# AC_controller_2020-08-26_13-25-38.net
KiCad netlist of a schematic drawn in EasyEDA
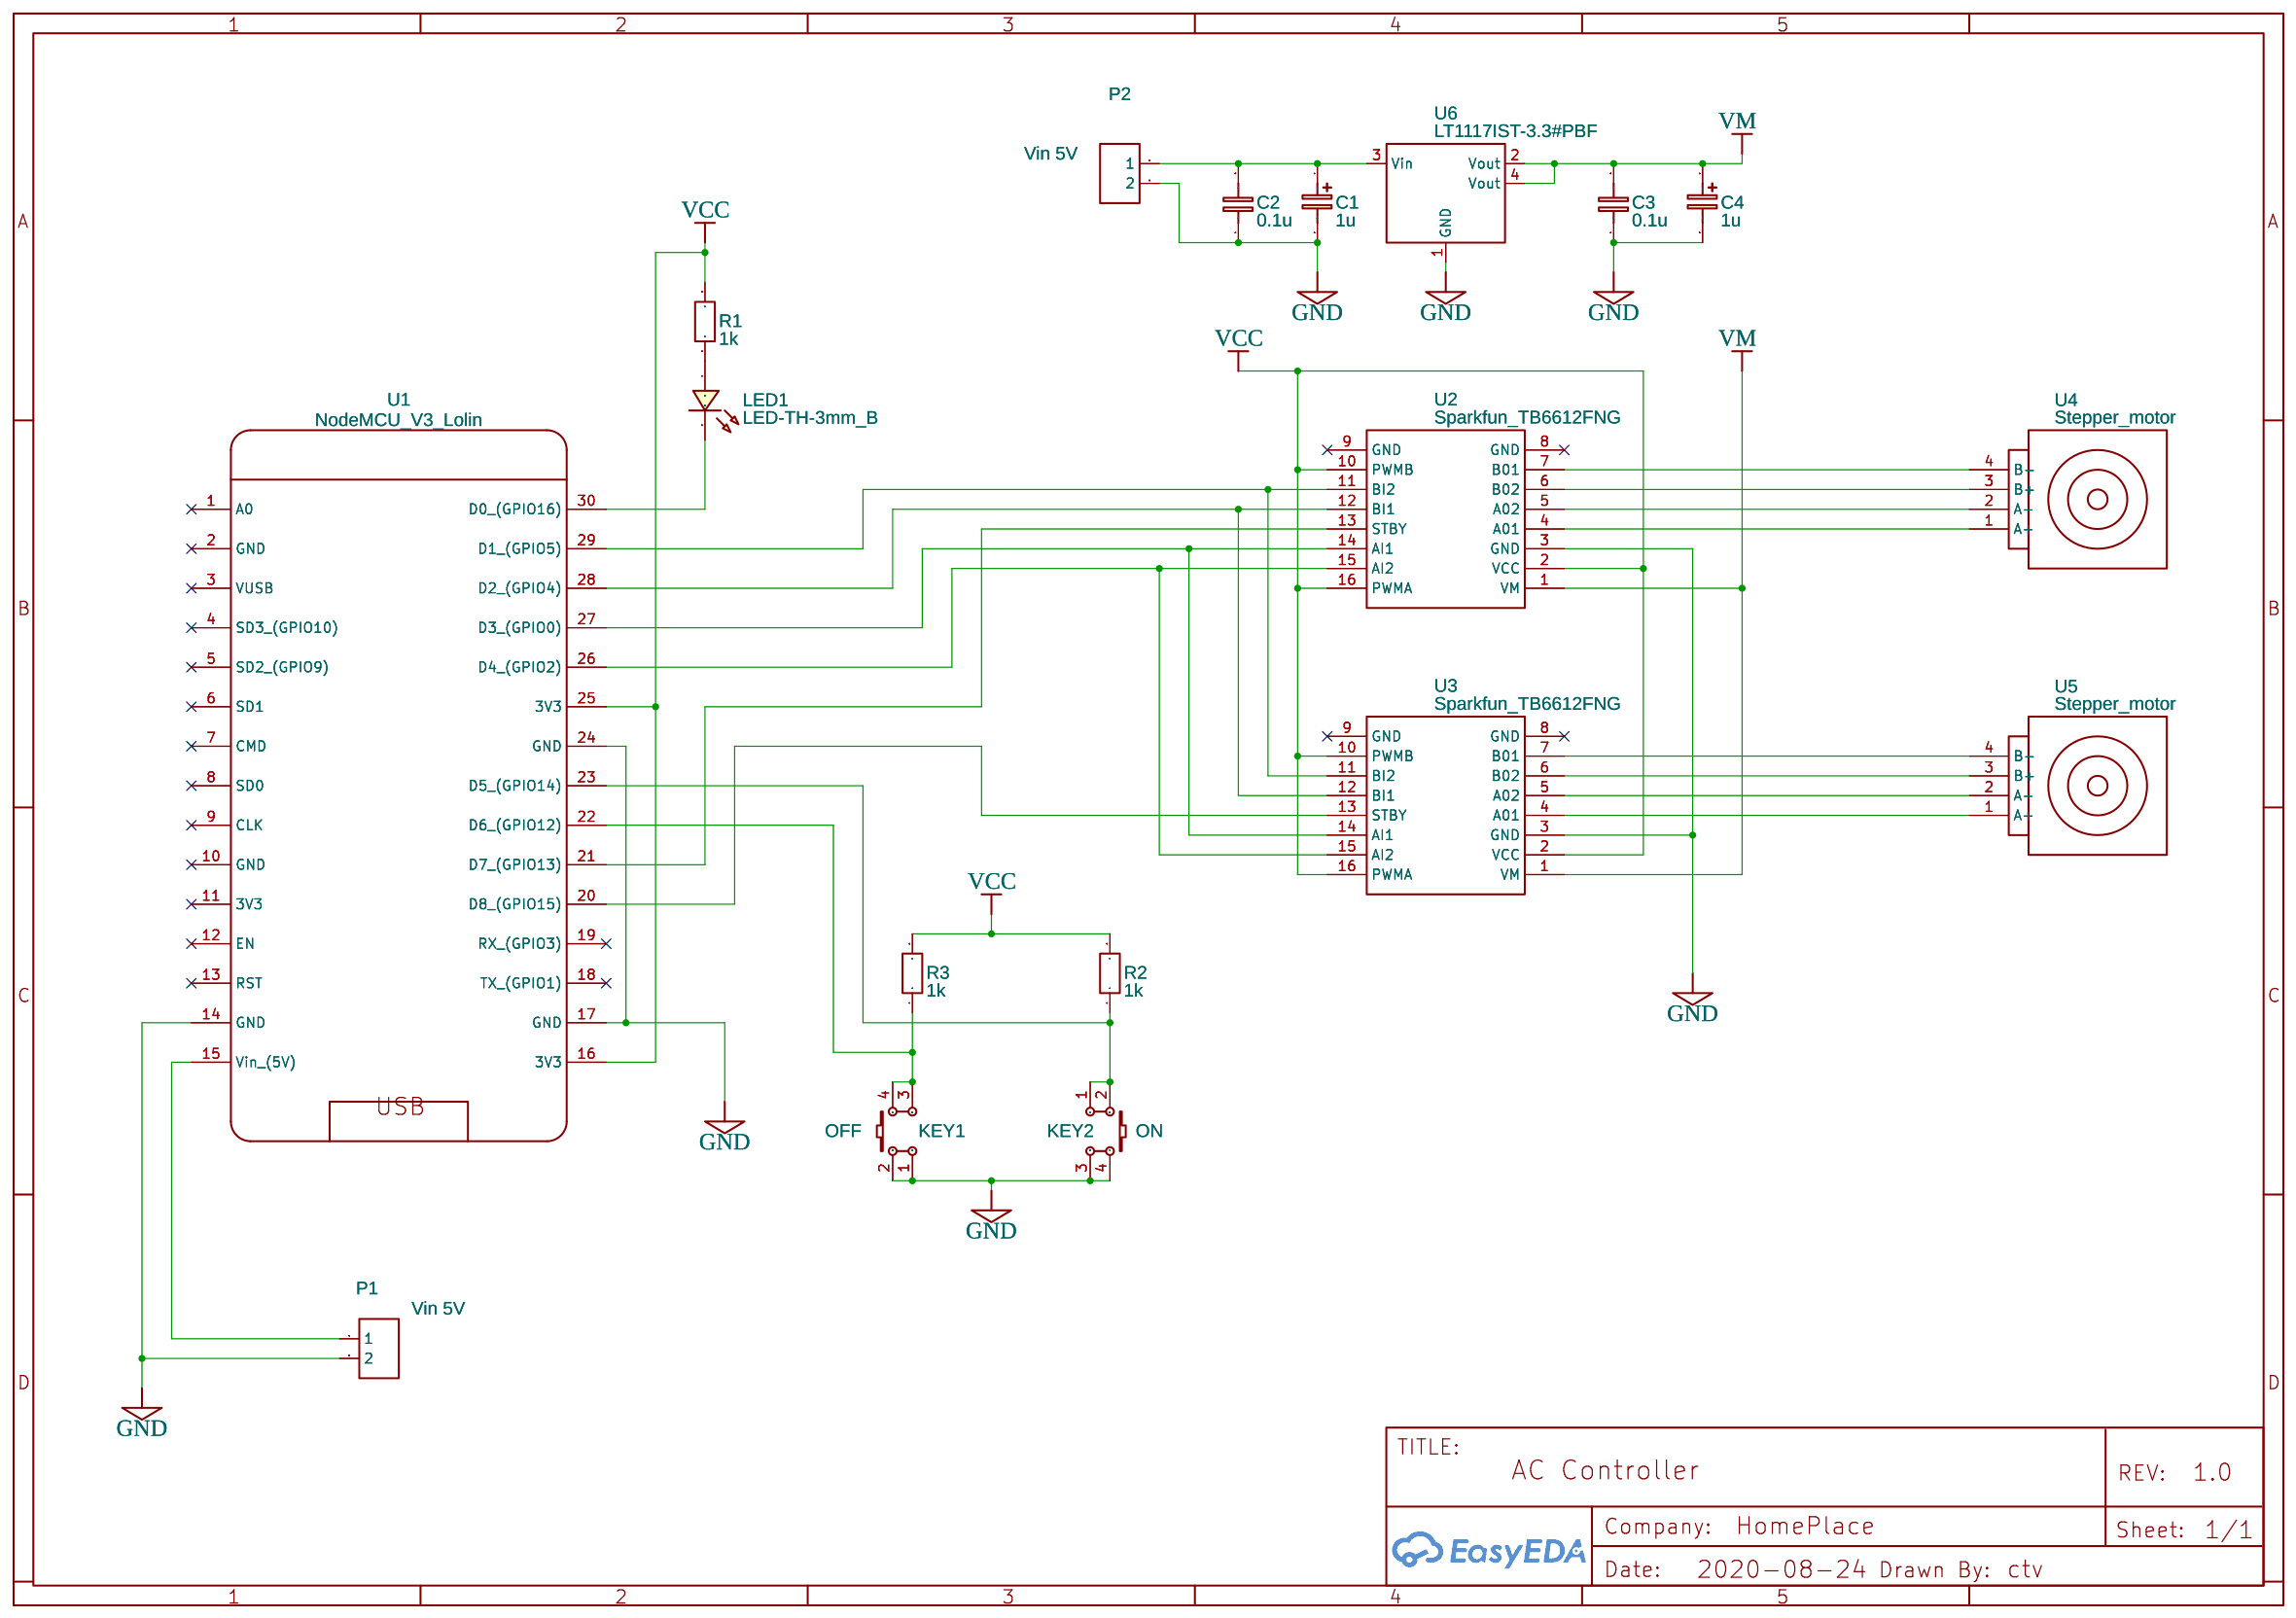
[diagram p0: schematic sheet]

(export (version "E")
  (design (tool "Eeschema 10.0.6"))
  (components
    (comp (ref "C1") (value "1u") (libsource (lib "") (part "C_Tan_SMD_A_EU")))
    (comp (ref "C2") (value "0.1u") (libsource (lib "") (part "C_0603_EU")))
    (comp (ref "C3") (value "0.1u") (libsource (lib "") (part "C_0603_EU")))
    (comp (ref "C4") (value "1u") (libsource (lib "") (part "C_Tan_SMD_A_EU")))
    (comp (ref "KEY1")
      (value "OFF")
      (fields
        (field (name "BOM_Manufacturer Part") "K2-1103DP-M4SW-04")
        (field (name "BOM_Supplier Part") "C128053")
      )
      (libsource (lib "") (part "K4-12×12_TH"))
    )
    (comp (ref "KEY2")
      (value "ON")
      (fields
        (field (name "BOM_Manufacturer Part") "K2-1103DP-M4SW-04")
        (field (name "BOM_Supplier Part") "C128053")
      )
      (libsource (lib "") (part "K4-12×12_TH_1"))
    )
    (comp (ref "LED1")
      (value "LED-TH-3mm_B")
      (fields
        (field (name "BOM_Manufacturer Part") "204-10SUBC/S400-A4")
        (field (name "BOM_Supplier Part") "C86881")
      )
      (libsource (lib "") (part "LED-TH-3mm_B"))
    )
    (comp (ref "P1") (value "Vin 5V") (libsource (lib "") (part "CONN-TH_2P-P5.08_1")))
    (comp (ref "P2") (value "Vin 5V") (libsource (lib "") (part "CONN-TH_2P-P5.08")))
    (comp (ref "R1") (value "1k") (libsource (lib "") (part "R_0603_EU")))
    (comp (ref "R2") (value "1k") (libsource (lib "") (part "R_0603_EU")))
    (comp (ref "R3") (value "1k") (libsource (lib "") (part "R_0603_EU")))
    (comp (ref "U1")
      (value "NodeMCU_V3_Lolin")
      (fields (field (name "BOM_Manufacturer Part") "NodeMCU ESP8266-12E Amica V2"))
      (libsource (lib "") (part "NodeMCU_ESP8266-12E_Lolin"))
    )
    (comp (ref "U2") (value "Sparkfun_TB6612FNG") (libsource (lib "") (part "Sparkfun_TB6612FNG")))
    (comp (ref "U3") (value "Sparkfun_TB6612FNG") (libsource (lib "") (part "Sparkfun_TB6612FNG")))
    (comp (ref "U4")
      (value "Stepper_motor")
      (fields (field (name "BOM_Manufacturer Part") "NEMA 23 Stepper Motor"))
      (libsource (lib "") (part "Stepper_motor"))
    )
    (comp (ref "U5")
      (value "Stepper_motor")
      (fields (field (name "BOM_Manufacturer Part") "NEMA 23 Stepper Motor"))
      (libsource (lib "") (part "Stepper_motor"))
    )
    (comp (ref "U6")
      (value "LT1117IST-3.3#PBF")
      (fields (field (name "BOM_Supplier Part") "C114908"))
      (libsource (lib "") (part "LT1117IST-3.3#PBF"))
    )
  )
  (nets
    (net (code "1") (name "GND") (class "Default")
      (node (ref "C1") (pin "2") (pinfunction "2_2") (pintype "unspecified"))
      (node (ref "C2") (pin "1") (pinfunction "1_1") (pintype "unspecified"))
      (node (ref "C3") (pin "1") (pinfunction "1_1") (pintype "unspecified"))
      (node (ref "C4") (pin "2") (pinfunction "2_2") (pintype "unspecified"))
      (node (ref "KEY1") (pin "1") (pinfunction "1_1") (pintype "unspecified"))
      (node (ref "KEY1") (pin "2") (pinfunction "2_2") (pintype "unspecified"))
      (node (ref "KEY2") (pin "3") (pinfunction "3_3") (pintype "unspecified"))
      (node (ref "KEY2") (pin "4") (pinfunction "4_4") (pintype "unspecified"))
      (node (ref "P1") (pin "2") (pinfunction "2_2") (pintype "unspecified"))
      (node (ref "P2") (pin "2") (pinfunction "2_2") (pintype "unspecified"))
      (node (ref "U1") (pin "14") (pinfunction "GND_14") (pintype "unspecified"))
      (node (ref "U1") (pin "17") (pinfunction "GND_17") (pintype "unspecified"))
      (node (ref "U1") (pin "24") (pinfunction "GND_24") (pintype "unspecified"))
      (node (ref "U2") (pin "3") (pinfunction "GND_3") (pintype "unspecified"))
      (node (ref "U3") (pin "3") (pinfunction "GND_3") (pintype "unspecified"))
      (node (ref "U6") (pin "1") (pinfunction "GND_1") (pintype "unspecified"))
    )
    (net (code "2") (name "Net-(LED1-Pad1)") (class "Default")
      (node (ref "LED1") (pin "1") (pinfunction "1_1") (pintype "unspecified"))
      (node (ref "R1") (pin "1") (pinfunction "1_1") (pintype "unspecified"))
    )
    (net (code "3") (name "Net-(U1-D0_(GPIO16))") (class "Default")
      (node (ref "LED1") (pin "2") (pinfunction "2_2") (pintype "unspecified"))
      (node (ref "U1") (pin "30") (pinfunction "D0_(GPIO16)_30") (pintype "unspecified"))
    )
    (net (code "4") (name "Net-(U1-D1_(GPIO5))") (class "Default")
      (node (ref "U1") (pin "29") (pinfunction "D1_(GPIO5)_29") (pintype "unspecified"))
      (node (ref "U2") (pin "11") (pinfunction "BI2_11") (pintype "unspecified"))
      (node (ref "U3") (pin "11") (pinfunction "BI2_11") (pintype "unspecified"))
    )
    (net (code "5") (name "Net-(U1-D2_(GPIO4))") (class "Default")
      (node (ref "U1") (pin "28") (pinfunction "D2_(GPIO4)_28") (pintype "unspecified"))
      (node (ref "U2") (pin "12") (pinfunction "BI1_12") (pintype "unspecified"))
      (node (ref "U3") (pin "12") (pinfunction "BI1_12") (pintype "unspecified"))
    )
    (net (code "6") (name "Net-(U1-D3_(GPIO0))") (class "Default")
      (node (ref "U1") (pin "27") (pinfunction "D3_(GPIO0)_27") (pintype "unspecified"))
      (node (ref "U2") (pin "14") (pinfunction "AI1_14") (pintype "unspecified"))
      (node (ref "U3") (pin "14") (pinfunction "AI1_14") (pintype "unspecified"))
    )
    (net (code "7") (name "Net-(U1-D4_(GPIO2))") (class "Default")
      (node (ref "U1") (pin "26") (pinfunction "D4_(GPIO2)_26") (pintype "unspecified"))
      (node (ref "U2") (pin "15") (pinfunction "AI2_15") (pintype "unspecified"))
      (node (ref "U3") (pin "15") (pinfunction "AI2_15") (pintype "unspecified"))
    )
    (net (code "8") (name "Net-(U1-D5_(GPIO14))") (class "Default")
      (node (ref "KEY2") (pin "1") (pinfunction "1_1") (pintype "unspecified"))
      (node (ref "KEY2") (pin "2") (pinfunction "2_2") (pintype "unspecified"))
      (node (ref "R2") (pin "1") (pinfunction "1_1") (pintype "unspecified"))
      (node (ref "U1") (pin "23") (pinfunction "D5_(GPIO14)_23") (pintype "unspecified"))
    )
    (net (code "9") (name "Net-(U1-D6_(GPIO12))") (class "Default")
      (node (ref "KEY1") (pin "3") (pinfunction "3_3") (pintype "unspecified"))
      (node (ref "KEY1") (pin "4") (pinfunction "4_4") (pintype "unspecified"))
      (node (ref "R3") (pin "1") (pinfunction "1_1") (pintype "unspecified"))
      (node (ref "U1") (pin "22") (pinfunction "D6_(GPIO12)_22") (pintype "unspecified"))
    )
    (net (code "10") (name "Net-(U1-D7_(GPIO13))") (class "Default")
      (node (ref "U1") (pin "21") (pinfunction "D7_(GPIO13)_21") (pintype "unspecified"))
      (node (ref "U2") (pin "13") (pinfunction "STBY_13") (pintype "unspecified"))
    )
    (net (code "11") (name "Net-(U1-D8_(GPIO15))") (class "Default")
      (node (ref "U1") (pin "20") (pinfunction "D8_(GPIO15)_20") (pintype "unspecified"))
      (node (ref "U3") (pin "13") (pinfunction "STBY_13") (pintype "unspecified"))
    )
    (net (code "12") (name "Net-(U1-Vin_(5V))") (class "Default")
      (node (ref "P1") (pin "1") (pinfunction "1_1") (pintype "unspecified"))
      (node (ref "U1") (pin "15") (pinfunction "Vin_(5V)_15") (pintype "unspecified"))
    )
    (net (code "13") (name "Net-(U2-A01)") (class "Default")
      (node (ref "U2") (pin "4") (pinfunction "A01_4") (pintype "unspecified"))
      (node (ref "U4") (pin "1") (pinfunction "A+_1") (pintype "unspecified"))
    )
    (net (code "14") (name "Net-(U2-A02)") (class "Default")
      (node (ref "U2") (pin "5") (pinfunction "A02_5") (pintype "unspecified"))
      (node (ref "U4") (pin "2") (pinfunction "A-_2") (pintype "unspecified"))
    )
    (net (code "15") (name "Net-(U2-B01)") (class "Default")
      (node (ref "U2") (pin "7") (pinfunction "B01_7") (pintype "unspecified"))
      (node (ref "U4") (pin "4") (pinfunction "B-_4") (pintype "unspecified"))
    )
    (net (code "16") (name "Net-(U2-B02)") (class "Default")
      (node (ref "U2") (pin "6") (pinfunction "B02_6") (pintype "unspecified"))
      (node (ref "U4") (pin "3") (pinfunction "B+_3") (pintype "unspecified"))
    )
    (net (code "17") (name "Net-(U3-A01)") (class "Default")
      (node (ref "U3") (pin "4") (pinfunction "A01_4") (pintype "unspecified"))
      (node (ref "U5") (pin "1") (pinfunction "A+_1") (pintype "unspecified"))
    )
    (net (code "18") (name "Net-(U3-A02)") (class "Default")
      (node (ref "U3") (pin "5") (pinfunction "A02_5") (pintype "unspecified"))
      (node (ref "U5") (pin "2") (pinfunction "A-_2") (pintype "unspecified"))
    )
    (net (code "19") (name "Net-(U3-B01)") (class "Default")
      (node (ref "U3") (pin "7") (pinfunction "B01_7") (pintype "unspecified"))
      (node (ref "U5") (pin "4") (pinfunction "B-_4") (pintype "unspecified"))
    )
    (net (code "20") (name "Net-(U3-B02)") (class "Default")
      (node (ref "U3") (pin "6") (pinfunction "B02_6") (pintype "unspecified"))
      (node (ref "U5") (pin "3") (pinfunction "B+_3") (pintype "unspecified"))
    )
    (net (code "21") (name "Net-(U6-Vin)") (class "Default")
      (node (ref "C1") (pin "1") (pinfunction "1_1") (pintype "unspecified"))
      (node (ref "C2") (pin "2") (pinfunction "2_2") (pintype "unspecified"))
      (node (ref "P2") (pin "1") (pinfunction "1_1") (pintype "unspecified"))
      (node (ref "U6") (pin "3") (pinfunction "Vin_3") (pintype "passive"))
    )
    (net (code "22") (name "VCC") (class "Default")
      (node (ref "R1") (pin "2") (pinfunction "2_2") (pintype "unspecified"))
      (node (ref "R2") (pin "2") (pinfunction "2_2") (pintype "unspecified"))
      (node (ref "R3") (pin "2") (pinfunction "2_2") (pintype "unspecified"))
      (node (ref "U1") (pin "16") (pinfunction "3V3_16") (pintype "unspecified"))
      (node (ref "U1") (pin "25") (pinfunction "3V3_25") (pintype "unspecified"))
      (node (ref "U2") (pin "10") (pinfunction "PWMB_10") (pintype "unspecified"))
      (node (ref "U2") (pin "16") (pinfunction "PWMA_16") (pintype "unspecified"))
      (node (ref "U2") (pin "2") (pinfunction "VCC_2") (pintype "unspecified"))
      (node (ref "U3") (pin "10") (pinfunction "PWMB_10") (pintype "unspecified"))
      (node (ref "U3") (pin "16") (pinfunction "PWMA_16") (pintype "unspecified"))
      (node (ref "U3") (pin "2") (pinfunction "VCC_2") (pintype "unspecified"))
    )
    (net (code "23") (name "VM") (class "Default")
      (node (ref "C3") (pin "2") (pinfunction "2_2") (pintype "unspecified"))
      (node (ref "C4") (pin "1") (pinfunction "1_1") (pintype "unspecified"))
      (node (ref "U2") (pin "1") (pinfunction "VM_1") (pintype "unspecified"))
      (node (ref "U3") (pin "1") (pinfunction "VM_1") (pintype "unspecified"))
      (node (ref "U6") (pin "2") (pinfunction "Vout_2") (pintype "unspecified"))
      (node (ref "U6") (pin "4") (pinfunction "Vout_4") (pintype "unspecified"))
    )
    (net (code "24") (name "unconnected-(U1-3V3-Pad11)") (class "Default")
      (node (ref "U1") (pin "11") (pinfunction "3V3_11") (pintype "unspecified+no_connect"))
    )
    (net (code "25") (name "unconnected-(U1-A0-Pad1)") (class "Default")
      (node (ref "U1") (pin "1") (pinfunction "A0_1") (pintype "unspecified+no_connect"))
    )
    (net (code "26") (name "unconnected-(U1-CLK-Pad9)") (class "Default")
      (node (ref "U1") (pin "9") (pinfunction "CLK_9") (pintype "unspecified+no_connect"))
    )
    (net (code "27") (name "unconnected-(U1-CMD-Pad7)") (class "Default")
      (node (ref "U1") (pin "7") (pinfunction "CMD_7") (pintype "unspecified+no_connect"))
    )
    (net (code "28") (name "unconnected-(U1-EN-Pad12)") (class "Default")
      (node (ref "U1") (pin "12") (pinfunction "EN_12") (pintype "unspecified+no_connect"))
    )
    (net (code "29") (name "unconnected-(U1-GND-Pad2)") (class "Default")
      (node (ref "U1") (pin "2") (pinfunction "GND_2") (pintype "unspecified+no_connect"))
    )
    (net (code "30") (name "unconnected-(U1-GND-Pad10)") (class "Default")
      (node (ref "U1") (pin "10") (pinfunction "GND_10") (pintype "unspecified+no_connect"))
    )
    (net (code "31") (name "unconnected-(U1-RST-Pad13)") (class "Default")
      (node (ref "U1") (pin "13") (pinfunction "RST_13") (pintype "unspecified+no_connect"))
    )
    (net (code "32") (name "unconnected-(U1-RX_(GPIO3)-Pad19)") (class "Default")
      (node (ref "U1") (pin "19") (pinfunction "RX_(GPIO3)_19") (pintype "unspecified+no_connect"))
    )
    (net (code "33") (name "unconnected-(U1-SD0-Pad8)") (class "Default")
      (node (ref "U1") (pin "8") (pinfunction "SD0_8") (pintype "unspecified+no_connect"))
    )
    (net (code "34") (name "unconnected-(U1-SD1-Pad6)") (class "Default")
      (node (ref "U1") (pin "6") (pinfunction "SD1_6") (pintype "unspecified+no_connect"))
    )
    (net (code "35") (name "unconnected-(U1-SD2_(GPIO9)-Pad5)") (class "Default")
      (node (ref "U1") (pin "5") (pinfunction "SD2_(GPIO9)_5") (pintype "unspecified+no_connect"))
    )
    (net (code "36") (name "unconnected-(U1-SD3_(GPIO10)-Pad4)") (class "Default")
      (node (ref "U1") (pin "4") (pinfunction "SD3_(GPIO10)_4") (pintype "unspecified+no_connect"))
    )
    (net (code "37") (name "unconnected-(U1-TX_(GPIO1)-Pad18)") (class "Default")
      (node (ref "U1") (pin "18") (pinfunction "TX_(GPIO1)_18") (pintype "unspecified+no_connect"))
    )
    (net (code "38") (name "unconnected-(U1-VUSB-Pad3)") (class "Default")
      (node (ref "U1") (pin "3") (pinfunction "VUSB_3") (pintype "unspecified+no_connect"))
    )
    (net (code "39") (name "unconnected-(U2-GND-Pad8)") (class "Default")
      (node (ref "U2") (pin "8") (pinfunction "GND_8") (pintype "unspecified+no_connect"))
    )
    (net (code "40") (name "unconnected-(U2-GND-Pad9)") (class "Default")
      (node (ref "U2") (pin "9") (pinfunction "GND_9") (pintype "unspecified+no_connect"))
    )
    (net (code "41") (name "unconnected-(U3-GND-Pad8)") (class "Default")
      (node (ref "U3") (pin "8") (pinfunction "GND_8") (pintype "unspecified+no_connect"))
    )
    (net (code "42") (name "unconnected-(U3-GND-Pad9)") (class "Default")
      (node (ref "U3") (pin "9") (pinfunction "GND_9") (pintype "unspecified+no_connect"))
    )
  )
)
